# IRreceiver.net
KiCad netlist of a schematic drawn in EAGLE
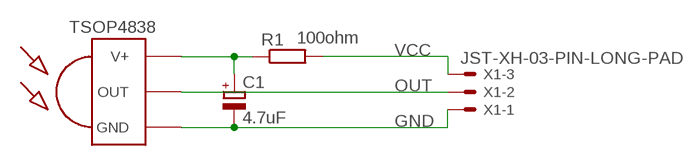
[diagram p0: schematic, sheet 1]

(export (version "E")
  (design (tool "Eeschema 10.0.6"))
  (components
    (comp (ref "C1")
      (value "4.7uF")
      (footprint "eagle-import:153CLV-0405")
      (libsource (lib "eagle-import") (part "CPOL-EU153CLV-0405"))
    )
    (comp (ref "R1")
      (value "100ohm")
      (footprint "eagle-import:R0805")
      (libsource (lib "eagle-import") (part "R-EU_R0805"))
    )
    (comp (ref "U$1")
      (value "TSOP4838")
      (footprint "eagle-import:TSOP18XX")
      (libsource (lib "eagle-import") (part "TSOP4838"))
    )
    (comp (ref "X1")
      (value "JST-XH-03-PIN-LONG-PAD")
      (footprint "eagle-import:JST-XH-03-PACKAGE-LONG-PAD")
      (libsource (lib "eagle-import") (part "JST-XH-03-PIN-LONG-PAD"))
    )
  )
  (nets
    (net (code "1") (name "/GND") (class "Default")
      (node (ref "C1") (pin "-") (pinfunction "-_-") (pintype "passive"))
      (node (ref "U$1") (pin "GND") (pinfunction "GND_GND") (pintype "bidirectional"))
      (node (ref "X1") (pin "1") (pinfunction "S_1") (pintype "passive"))
    )
    (net (code "2") (name "/OUT") (class "Default")
      (node (ref "U$1") (pin "OUT") (pinfunction "OUT_OUT") (pintype "bidirectional"))
      (node (ref "X1") (pin "2") (pinfunction "S_2") (pintype "passive"))
    )
    (net (code "3") (name "/VCC") (class "Default")
      (node (ref "R1") (pin "2") (pinfunction "2_2") (pintype "passive"))
      (node (ref "X1") (pin "3") (pinfunction "S_3") (pintype "passive"))
    )
    (net (code "4") (name "Net-(U$1-V+)") (class "Default")
      (node (ref "C1") (pin "+") (pinfunction "+_+") (pintype "passive"))
      (node (ref "R1") (pin "1") (pinfunction "1_1") (pintype "passive"))
      (node (ref "U$1") (pin "VCC") (pinfunction "V+_VCC") (pintype "bidirectional"))
    )
  )
)
